# debug-port-breakout.net
KiCad netlist of a schematic drawn in EAGLE
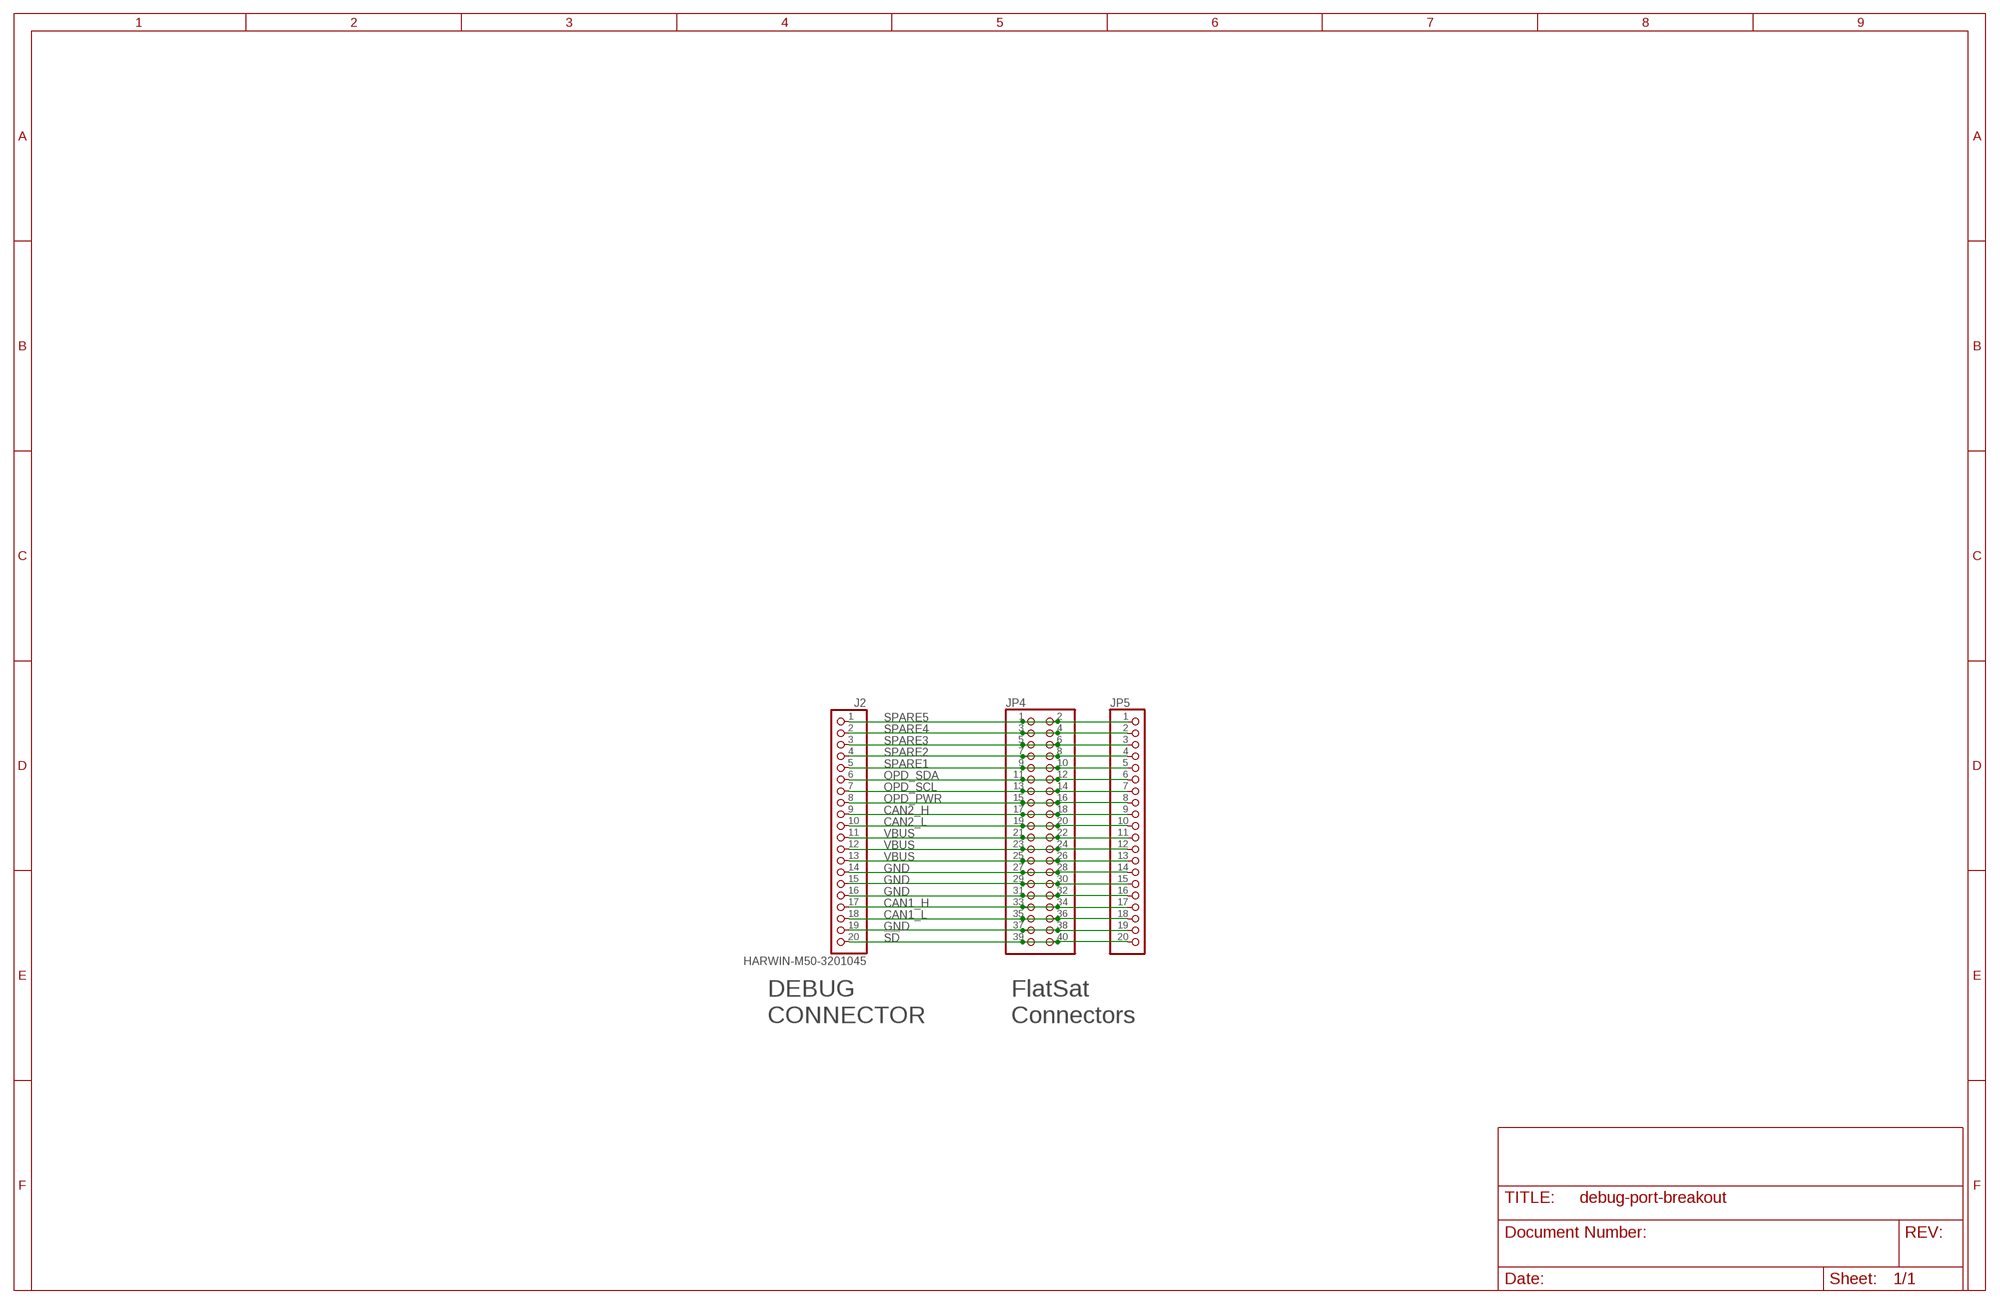
[diagram p0: schematic, sheet 1]

(export (version "E")
  (design (tool "Eeschema 10.0.6"))
  (components
    (comp (ref "J2")
      (value "HARWIN-M50-3201045")
      (footprint "eagle-import:HARWIN-M50-3201045")
      (libsource (lib "eagle-import") (part "HARWIN-M50-3201045"))
    )
    (comp (ref "JP4")
      (value "PINHD-2X20")
      (footprint "eagle-import:2X20")
      (libsource (lib "eagle-import") (part "PINHD-2X20"))
    )
    (comp (ref "JP5")
      (value "PINHD-1X20")
      (footprint "eagle-import:1X20")
      (libsource (lib "eagle-import") (part "PINHD-1X20"))
    )
  )
  (nets
    (net (code "1") (name "/CAN1_H") (class "Default")
      (node (ref "J2") (pin "17") (pinfunction "17_17") (pintype "passive"))
      (node (ref "JP4") (pin "33") (pinfunction "33_33") (pintype "passive"))
      (node (ref "JP4") (pin "34") (pinfunction "34_34") (pintype "passive"))
      (node (ref "JP5") (pin "17") (pinfunction "17_17") (pintype "passive"))
    )
    (net (code "2") (name "/CAN1_L") (class "Default")
      (node (ref "J2") (pin "18") (pinfunction "18_18") (pintype "passive"))
      (node (ref "JP4") (pin "35") (pinfunction "35_35") (pintype "passive"))
      (node (ref "JP4") (pin "36") (pinfunction "36_36") (pintype "passive"))
      (node (ref "JP5") (pin "18") (pinfunction "18_18") (pintype "passive"))
    )
    (net (code "3") (name "/CAN2_H") (class "Default")
      (node (ref "J2") (pin "9") (pinfunction "9_9") (pintype "passive"))
      (node (ref "JP4") (pin "17") (pinfunction "17_17") (pintype "passive"))
      (node (ref "JP4") (pin "18") (pinfunction "18_18") (pintype "passive"))
      (node (ref "JP5") (pin "9") (pinfunction "9_9") (pintype "passive"))
    )
    (net (code "4") (name "/CAN2_L") (class "Default")
      (node (ref "J2") (pin "10") (pinfunction "10_10") (pintype "passive"))
      (node (ref "JP4") (pin "19") (pinfunction "19_19") (pintype "passive"))
      (node (ref "JP4") (pin "20") (pinfunction "20_20") (pintype "passive"))
      (node (ref "JP5") (pin "10") (pinfunction "10_10") (pintype "passive"))
    )
    (net (code "5") (name "/GND") (class "Default")
      (node (ref "J2") (pin "14") (pinfunction "14_14") (pintype "passive"))
      (node (ref "J2") (pin "15") (pinfunction "15_15") (pintype "passive"))
      (node (ref "J2") (pin "16") (pinfunction "16_16") (pintype "passive"))
      (node (ref "J2") (pin "19") (pinfunction "19_19") (pintype "passive"))
      (node (ref "JP4") (pin "27") (pinfunction "27_27") (pintype "passive"))
      (node (ref "JP4") (pin "28") (pinfunction "28_28") (pintype "passive"))
      (node (ref "JP4") (pin "29") (pinfunction "29_29") (pintype "passive"))
      (node (ref "JP4") (pin "30") (pinfunction "30_30") (pintype "passive"))
      (node (ref "JP4") (pin "31") (pinfunction "31_31") (pintype "passive"))
      (node (ref "JP4") (pin "32") (pinfunction "32_32") (pintype "passive"))
      (node (ref "JP4") (pin "37") (pinfunction "37_37") (pintype "passive"))
      (node (ref "JP4") (pin "38") (pinfunction "38_38") (pintype "passive"))
      (node (ref "JP5") (pin "14") (pinfunction "14_14") (pintype "passive"))
      (node (ref "JP5") (pin "15") (pinfunction "15_15") (pintype "passive"))
      (node (ref "JP5") (pin "16") (pinfunction "16_16") (pintype "passive"))
      (node (ref "JP5") (pin "19") (pinfunction "19_19") (pintype "passive"))
    )
    (net (code "6") (name "/OPD_PWR") (class "Default")
      (node (ref "J2") (pin "8") (pinfunction "8_8") (pintype "passive"))
      (node (ref "JP4") (pin "15") (pinfunction "15_15") (pintype "passive"))
      (node (ref "JP4") (pin "16") (pinfunction "16_16") (pintype "passive"))
      (node (ref "JP5") (pin "8") (pinfunction "8_8") (pintype "passive"))
    )
    (net (code "7") (name "/OPD_SCL") (class "Default")
      (node (ref "J2") (pin "7") (pinfunction "7_7") (pintype "passive"))
      (node (ref "JP4") (pin "13") (pinfunction "13_13") (pintype "passive"))
      (node (ref "JP4") (pin "14") (pinfunction "14_14") (pintype "passive"))
      (node (ref "JP5") (pin "7") (pinfunction "7_7") (pintype "passive"))
    )
    (net (code "8") (name "/OPD_SDA") (class "Default")
      (node (ref "J2") (pin "6") (pinfunction "6_6") (pintype "passive"))
      (node (ref "JP4") (pin "11") (pinfunction "11_11") (pintype "passive"))
      (node (ref "JP4") (pin "12") (pinfunction "12_12") (pintype "passive"))
      (node (ref "JP5") (pin "6") (pinfunction "6_6") (pintype "passive"))
    )
    (net (code "9") (name "/SPARE1") (class "Default")
      (node (ref "J2") (pin "5") (pinfunction "5_5") (pintype "passive"))
      (node (ref "JP4") (pin "10") (pinfunction "10_10") (pintype "passive"))
      (node (ref "JP4") (pin "9") (pinfunction "9_9") (pintype "passive"))
      (node (ref "JP5") (pin "5") (pinfunction "5_5") (pintype "passive"))
    )
    (net (code "10") (name "/SPARE2") (class "Default")
      (node (ref "J2") (pin "4") (pinfunction "4_4") (pintype "passive"))
      (node (ref "JP4") (pin "7") (pinfunction "7_7") (pintype "passive"))
      (node (ref "JP4") (pin "8") (pinfunction "8_8") (pintype "passive"))
      (node (ref "JP5") (pin "4") (pinfunction "4_4") (pintype "passive"))
    )
    (net (code "11") (name "/SPARE3") (class "Default")
      (node (ref "J2") (pin "3") (pinfunction "3_3") (pintype "passive"))
      (node (ref "JP4") (pin "5") (pinfunction "5_5") (pintype "passive"))
      (node (ref "JP4") (pin "6") (pinfunction "6_6") (pintype "passive"))
      (node (ref "JP5") (pin "3") (pinfunction "3_3") (pintype "passive"))
    )
    (net (code "12") (name "/SPARE4") (class "Default")
      (node (ref "J2") (pin "2") (pinfunction "2_2") (pintype "passive"))
      (node (ref "JP4") (pin "3") (pinfunction "3_3") (pintype "passive"))
      (node (ref "JP4") (pin "4") (pinfunction "4_4") (pintype "passive"))
      (node (ref "JP5") (pin "2") (pinfunction "2_2") (pintype "passive"))
    )
    (net (code "13") (name "/SPARE5") (class "Default")
      (node (ref "J2") (pin "1") (pinfunction "1_1") (pintype "passive"))
      (node (ref "JP4") (pin "1") (pinfunction "1_1") (pintype "passive"))
      (node (ref "JP4") (pin "2") (pinfunction "2_2") (pintype "passive"))
      (node (ref "JP5") (pin "1") (pinfunction "1_1") (pintype "passive"))
    )
    (net (code "14") (name "/VBUS") (class "Default")
      (node (ref "J2") (pin "11") (pinfunction "11_11") (pintype "passive"))
      (node (ref "J2") (pin "12") (pinfunction "12_12") (pintype "passive"))
      (node (ref "J2") (pin "13") (pinfunction "13_13") (pintype "passive"))
      (node (ref "JP4") (pin "21") (pinfunction "21_21") (pintype "passive"))
      (node (ref "JP4") (pin "22") (pinfunction "22_22") (pintype "passive"))
      (node (ref "JP4") (pin "23") (pinfunction "23_23") (pintype "passive"))
      (node (ref "JP4") (pin "24") (pinfunction "24_24") (pintype "passive"))
      (node (ref "JP4") (pin "25") (pinfunction "25_25") (pintype "passive"))
      (node (ref "JP4") (pin "26") (pinfunction "26_26") (pintype "passive"))
      (node (ref "JP5") (pin "11") (pinfunction "11_11") (pintype "passive"))
      (node (ref "JP5") (pin "12") (pinfunction "12_12") (pintype "passive"))
      (node (ref "JP5") (pin "13") (pinfunction "13_13") (pintype "passive"))
    )
    (net (code "15") (name "/~{SD}") (class "Default")
      (node (ref "J2") (pin "20") (pinfunction "20_20") (pintype "passive"))
      (node (ref "JP4") (pin "39") (pinfunction "39_39") (pintype "passive"))
      (node (ref "JP4") (pin "40") (pinfunction "40_40") (pintype "passive"))
      (node (ref "JP5") (pin "20") (pinfunction "20_20") (pintype "passive"))
    )
  )
)
